# pH_EZO_2.net
KiCad netlist of a schematic drawn in Altium Designer
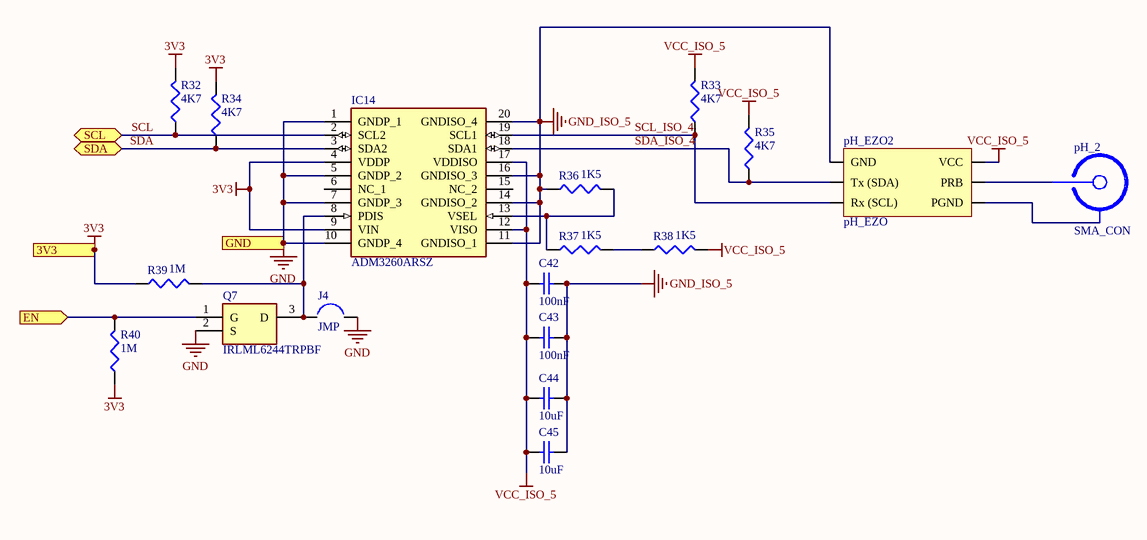
[diagram p0: pH_EZO_2.SchDoc]

(export (version "E")
  (design (tool "Eeschema 10.0.6"))
  (components
    (comp (ref "C42")
      (value "100nF")
      (footprint "1608[0603]")
      (description "Capacitor (Semiconductor SIM Model)")
      (fields (field (name "PUBLISHER") "Altium Limited"))
      (libsource (lib "Miscellaneous Devices") (part "Cap Semi"))
    )
    (comp (ref "C43")
      (value "100nF")
      (footprint "1608[0603]")
      (description "Capacitor (Semiconductor SIM Model)")
      (fields (field (name "PUBLISHER") "Altium Limited"))
      (libsource (lib "Miscellaneous Devices") (part "Cap Semi"))
    )
    (comp (ref "C44")
      (value "10uF")
      (footprint "1608[0603]")
      (description "Capacitor (Semiconductor SIM Model)")
      (fields (field (name "PUBLISHER") "Altium Limited"))
      (libsource (lib "Miscellaneous Devices") (part "Cap Semi"))
    )
    (comp (ref "C45")
      (value "10uF")
      (footprint "1608[0603]")
      (description "Capacitor (Semiconductor SIM Model)")
      (fields (field (name "PUBLISHER") "Altium Limited"))
      (libsource (lib "Miscellaneous Devices") (part "Cap Semi"))
    )
    (comp (ref "IC14")
      (value "ADM3260ARSZ")
      (footprint "SOP65P780X200-20N")
      (description "Integrated Circuit")
      (fields
        (field (name "MOUSER PART NUMBER") "584-ADM3260ARSZ")
        (field (name "RS PART NUMBER") "8319113P")
      )
      (libsource (lib "SamacSys") (part "ADM3260ARSZ"))
    )
    (comp (ref "J4") (value "JMP") (footprint "Jumper") (libsource (lib "SamacSys") (part "JMP")))
    (comp (ref "pH_2")
      (value "SMA_CON")
      (footprint "SamacSys:PCBSMAFRAHT")
      (description "Connector")
      (fields
        (field (name "MANUFACTURER_PART_NUMBER") "PCB.SMAFRA.HT")
        (field (name "MOUSER PART NUMBER") "960-PCB.SMAFRA.HT")
      )
      (libsource (lib "SamacSys") (part "SMA"))
    )
    (comp (ref "pH_EZO2") (value "pH_EZO") (footprint "Ph_ezo") (libsource (lib "SamacSys") (part "pH_EZO")))
    (comp (ref "Q7")
      (value "IRLML6244TRPBF")
      (footprint "SOT95P237X112-3N")
      (description "Transistor")
      (fields
        (field (name "MOUSER PART NUMBER") "942-IRLML6244TRPBF")
        (field (name "RS PART NUMBER") "7377228P")
      )
      (libsource (lib "SamacSys") (part "IRLML6244TRPBF"))
    )
    (comp (ref "R32")
      (value "4K7")
      (footprint "J1-0603")
      (description "Resistor")
      (fields (field (name "PUBLISHER") "Altium Limited"))
      (libsource (lib "Miscellaneous Devices") (part "Res3"))
    )
    (comp (ref "R33")
      (value "4K7")
      (footprint "J1-0603")
      (description "Resistor")
      (fields (field (name "PUBLISHER") "Altium Limited"))
      (libsource (lib "Miscellaneous Devices") (part "Res3"))
    )
    (comp (ref "R34")
      (value "4K7")
      (footprint "J1-0603")
      (description "Resistor")
      (fields (field (name "PUBLISHER") "Altium Limited"))
      (libsource (lib "Miscellaneous Devices") (part "Res3"))
    )
    (comp (ref "R35")
      (value "4K7")
      (footprint "J1-0603")
      (description "Resistor")
      (fields (field (name "PUBLISHER") "Altium Limited"))
      (libsource (lib "Miscellaneous Devices") (part "Res3"))
    )
    (comp (ref "R36")
      (value "1K5")
      (footprint "J1-0603")
      (description "Resistor")
      (fields (field (name "PUBLISHER") "Altium Limited"))
      (libsource (lib "Miscellaneous Devices") (part "Res3"))
    )
    (comp (ref "R37")
      (value "1K5")
      (footprint "J1-0603")
      (description "Resistor")
      (fields (field (name "PUBLISHER") "Altium Limited"))
      (libsource (lib "Miscellaneous Devices") (part "Res3"))
    )
    (comp (ref "R38")
      (value "1K5")
      (footprint "J1-0603")
      (description "Resistor")
      (fields (field (name "PUBLISHER") "Altium Limited"))
      (libsource (lib "Miscellaneous Devices") (part "Res3"))
    )
    (comp (ref "R39")
      (value "1M")
      (footprint "J1-0603")
      (description "Resistor")
      (fields (field (name "PUBLISHER") "Altium Limited"))
      (libsource (lib "Miscellaneous Devices") (part "Res3"))
    )
    (comp (ref "R40")
      (value "1M")
      (footprint "J1-0603")
      (description "Resistor")
      (fields (field (name "PUBLISHER") "Altium Limited"))
      (libsource (lib "Miscellaneous Devices") (part "Res3"))
    )
  )
  (nets
    (net (code "1") (name "/EN") (class "Default")
      (node (ref "Q7") (pin "1") (pinfunction "G_1") (pintype "passive"))
      (node (ref "R40") (pin "2") (pinfunction "2_2") (pintype "passive"))
    )
    (net (code "2") (name "/SCL") (class "Default")
      (node (ref "IC14") (pin "2") (pinfunction "SCL2_2") (pintype "bidirectional"))
      (node (ref "R32") (pin "1") (pinfunction "1_1") (pintype "passive"))
    )
    (net (code "3") (name "/SCL_ISO_4") (class "Default")
      (node (ref "IC14") (pin "19") (pinfunction "SCL1_19") (pintype "bidirectional"))
      (node (ref "R33") (pin "1") (pinfunction "1_1") (pintype "passive"))
      (node (ref "pH_EZO2") (pin "3") (pinfunction "Rx_(SCL)_3") (pintype "passive"))
    )
    (net (code "4") (name "/SDA") (class "Default")
      (node (ref "IC14") (pin "3") (pinfunction "SDA2_3") (pintype "bidirectional"))
      (node (ref "R34") (pin "1") (pinfunction "1_1") (pintype "passive"))
    )
    (net (code "5") (name "/SDA_ISO_4") (class "Default")
      (node (ref "IC14") (pin "18") (pinfunction "SDA1_18") (pintype "bidirectional"))
      (node (ref "R35") (pin "1") (pinfunction "1_1") (pintype "passive"))
      (node (ref "pH_EZO2") (pin "2") (pinfunction "Tx_(SDA)_2") (pintype "passive"))
    )
    (net (code "6") (name "3V3") (class "Default")
      (node (ref "IC14") (pin "4") (pinfunction "VDDP_4") (pintype "power_in"))
      (node (ref "IC14") (pin "9") (pinfunction "VIN_9") (pintype "power_in"))
      (node (ref "R32") (pin "2") (pinfunction "2_2") (pintype "passive"))
      (node (ref "R34") (pin "2") (pinfunction "2_2") (pintype "passive"))
      (node (ref "R39") (pin "1") (pinfunction "1_1") (pintype "passive"))
      (node (ref "R40") (pin "1") (pinfunction "1_1") (pintype "passive"))
    )
    (net (code "7") (name "GND") (class "Default")
      (node (ref "IC14") (pin "1") (pinfunction "GNDP_1_1") (pintype "power_in"))
      (node (ref "IC14") (pin "10") (pinfunction "GNDP_4_10") (pintype "power_in"))
      (node (ref "IC14") (pin "5") (pinfunction "GNDP_2_5") (pintype "power_in"))
      (node (ref "IC14") (pin "7") (pinfunction "GNDP_3_7") (pintype "power_in"))
      (node (ref "J4") (pin "2") (pinfunction "2_2") (pintype "passive"))
      (node (ref "Q7") (pin "2") (pinfunction "S_2") (pintype "passive"))
    )
    (net (code "8") (name "GND_ISO_5") (class "Default")
      (node (ref "C42") (pin "2") (pinfunction "2_2") (pintype "passive"))
      (node (ref "C43") (pin "2") (pinfunction "2_2") (pintype "passive"))
      (node (ref "C44") (pin "2") (pinfunction "2_2") (pintype "passive"))
      (node (ref "C45") (pin "2") (pinfunction "2_2") (pintype "passive"))
      (node (ref "IC14") (pin "11") (pinfunction "GNDISO_1_11") (pintype "power_in"))
      (node (ref "IC14") (pin "14") (pinfunction "GNDISO_2_14") (pintype "power_in"))
      (node (ref "IC14") (pin "16") (pinfunction "GNDISO_3_16") (pintype "power_in"))
      (node (ref "IC14") (pin "20") (pinfunction "GNDISO_4_20") (pintype "power_in"))
      (node (ref "R36") (pin "1") (pinfunction "1_1") (pintype "passive"))
      (node (ref "pH_EZO2") (pin "1") (pinfunction "GND_1") (pintype "passive"))
    )
    (net (code "9") (name "Net-(IC14-PDIS)") (class "Default")
      (node (ref "IC14") (pin "8") (pinfunction "PDIS_8") (pintype "input"))
      (node (ref "J4") (pin "1") (pinfunction "1_1") (pintype "passive"))
      (node (ref "Q7") (pin "3") (pinfunction "D_3") (pintype "passive"))
      (node (ref "R39") (pin "2") (pinfunction "2_2") (pintype "passive"))
    )
    (net (code "10") (name "Net-(IC14-VSEL)") (class "Default")
      (node (ref "IC14") (pin "13") (pinfunction "VSEL_13") (pintype "input"))
      (node (ref "R36") (pin "2") (pinfunction "2_2") (pintype "passive"))
      (node (ref "R37") (pin "1") (pinfunction "1_1") (pintype "passive"))
    )
    (net (code "11") (name "Net-(R37-Pad2)") (class "Default")
      (node (ref "R37") (pin "2") (pinfunction "2_2") (pintype "passive"))
      (node (ref "R38") (pin "1") (pinfunction "1_1") (pintype "passive"))
    )
    (net (code "12") (name "Net-(pH_EZO2-PGND)") (class "Default")
      (node (ref "pH_2") (pin "2") (pintype "passive"))
      (node (ref "pH_EZO2") (pin "6") (pinfunction "PGND_6") (pintype "passive"))
    )
    (net (code "13") (name "Net-(pH_EZO2-PRB)") (class "Default")
      (node (ref "pH_2") (pin "1") (pintype "passive"))
      (node (ref "pH_EZO2") (pin "5") (pinfunction "PRB_5") (pintype "passive"))
    )
    (net (code "14") (name "VCC_ISO_5") (class "Default")
      (node (ref "C42") (pin "1") (pinfunction "1_1") (pintype "passive"))
      (node (ref "C43") (pin "1") (pinfunction "1_1") (pintype "passive"))
      (node (ref "C44") (pin "1") (pinfunction "1_1") (pintype "passive"))
      (node (ref "C45") (pin "1") (pinfunction "1_1") (pintype "passive"))
      (node (ref "IC14") (pin "12") (pinfunction "VISO_12") (pintype "power_in"))
      (node (ref "IC14") (pin "17") (pinfunction "VDDISO_17") (pintype "power_in"))
      (node (ref "R33") (pin "2") (pinfunction "2_2") (pintype "passive"))
      (node (ref "R35") (pin "2") (pinfunction "2_2") (pintype "passive"))
      (node (ref "R38") (pin "2") (pinfunction "2_2") (pintype "passive"))
      (node (ref "pH_EZO2") (pin "4") (pinfunction "VCC_4") (pintype "passive"))
    )
    (net (code "15") (name "unconnected-(IC14-NC_1-Pad6)") (class "Default")
      (node (ref "IC14") (pin "6") (pinfunction "NC_1_6") (pintype "passive"))
    )
    (net (code "16") (name "unconnected-(IC14-NC_2-Pad15)") (class "Default")
      (node (ref "IC14") (pin "15") (pinfunction "NC_2_15") (pintype "passive"))
    )
  )
)
